# pressure.net
KiCad netlist of a schematic drawn in EAGLE
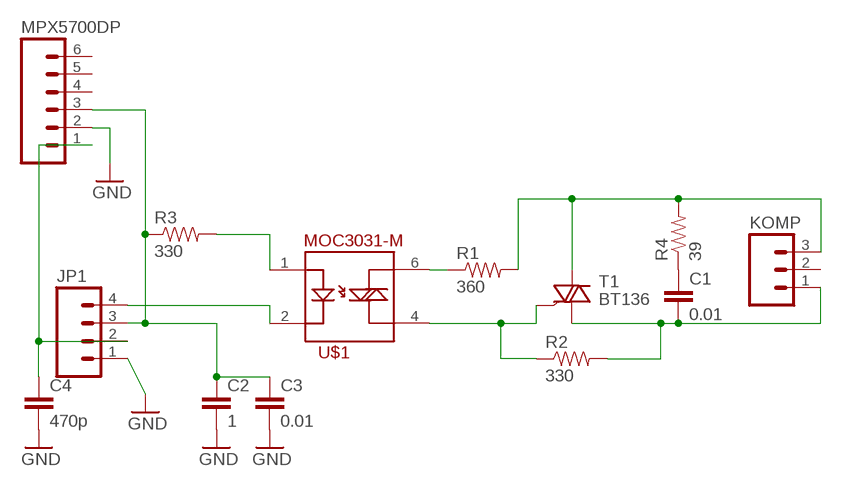
[diagram p0: schematic, sheet 1]

(export (version "E")
  (design (tool "Eeschema 10.0.6"))
  (components
    (comp (ref "C1")
      (value "0.01")
      (footprint "eagle-import:CAP-PTH-5MM")
      (libsource (lib "eagle-import") (part "CAPPTH1"))
    )
    (comp (ref "C2")
      (value "1")
      (footprint "eagle-import:CAP-PTH-5MM")
      (libsource (lib "eagle-import") (part "CAPPTH1"))
    )
    (comp (ref "C3")
      (value "0.01")
      (footprint "eagle-import:CAP-PTH-5MM")
      (libsource (lib "eagle-import") (part "CAPPTH1"))
    )
    (comp (ref "C4")
      (value "470p")
      (footprint "eagle-import:CAP-PTH-5MM")
      (libsource (lib "eagle-import") (part "CAPPTH1"))
    )
    (comp (ref "JP1")
      (value "M04LONGPADS")
      (footprint "eagle-import:1X04_LONGPADS")
      (libsource (lib "eagle-import") (part "M04LONGPADS"))
    )
    (comp (ref "KOMP")
      (value "M03LONGPADS")
      (footprint "eagle-import:1X03_LONGPADS")
      (libsource (lib "eagle-import") (part "M03LONGPADS"))
    )
    (comp (ref "MPX5700DP")
      (value "M06LONGPADS")
      (footprint "eagle-import:1X06_LONGPADS")
      (libsource (lib "eagle-import") (part "M06LONGPADS"))
    )
    (comp (ref "R1")
      (value "360")
      (footprint "eagle-import:AXIAL-0.3-KIT")
      (libsource (lib "eagle-import") (part "RESISTORKIT"))
    )
    (comp (ref "R2")
      (value "330")
      (footprint "eagle-import:AXIAL-0.3-KIT")
      (libsource (lib "eagle-import") (part "RESISTORKIT"))
    )
    (comp (ref "R3")
      (value "330")
      (footprint "eagle-import:AXIAL-0.3-KIT")
      (libsource (lib "eagle-import") (part "RESISTORKIT"))
    )
    (comp (ref "R4")
      (value "39")
      (footprint "eagle-import:AXIAL-0.3-KIT")
      (libsource (lib "eagle-import") (part "RESISTORKIT"))
    )
    (comp (ref "T1")
      (value "BT136")
      (footprint "eagle-import:TO220AB")
      (libsource (lib "eagle-import") (part "BT136"))
    )
    (comp (ref "U$1")
      (value "MOC3031-M")
      (footprint "eagle-import:DIL06")
      (libsource (lib "eagle-import") (part "MOC3031-M"))
    )
  )
  (nets
    (net (code "1") (name "GND") (class "Default")
      (node (ref "C2") (pin "2") (pinfunction "2_2") (pintype "passive"))
      (node (ref "C3") (pin "2") (pinfunction "2_2") (pintype "passive"))
      (node (ref "C4") (pin "2") (pinfunction "2_2") (pintype "passive"))
      (node (ref "JP1") (pin "1") (pinfunction "1_1") (pintype "passive"))
      (node (ref "MPX5700DP") (pin "2") (pinfunction "2_2") (pintype "passive"))
    )
    (net (code "2") (name "Net-(C4-Pad1)") (class "Default")
      (node (ref "C4") (pin "1") (pinfunction "1_1") (pintype "passive"))
      (node (ref "JP1") (pin "2") (pinfunction "2_2") (pintype "passive"))
      (node (ref "MPX5700DP") (pin "1") (pinfunction "1_1") (pintype "passive"))
    )
    (net (code "3") (name "Net-(JP1-Pad4)") (class "Default")
      (node (ref "JP1") (pin "4") (pinfunction "4_4") (pintype "passive"))
      (node (ref "U$1") (pin "2") (pinfunction "2_2") (pintype "bidirectional"))
    )
    (net (code "4") (name "Net-(R1-1)") (class "Default")
      (node (ref "R1") (pin "P$1") (pinfunction "1_P$1") (pintype "passive"))
      (node (ref "U$1") (pin "6") (pinfunction "6_6") (pintype "bidirectional"))
    )
    (net (code "5") (name "Net-(R1-2)") (class "Default")
      (node (ref "KOMP") (pin "3") (pinfunction "3_3") (pintype "passive"))
      (node (ref "R1") (pin "P$2") (pinfunction "2_P$2") (pintype "passive"))
      (node (ref "R4") (pin "P$2") (pinfunction "2_P$2") (pintype "passive"))
      (node (ref "T1") (pin "2") (pinfunction "A2_2") (pintype "passive"))
    )
    (net (code "6") (name "Net-(R2-1)") (class "Default")
      (node (ref "R2") (pin "P$1") (pinfunction "1_P$1") (pintype "passive"))
      (node (ref "T1") (pin "3") (pinfunction "G_3") (pintype "passive"))
      (node (ref "U$1") (pin "4") (pinfunction "4_4") (pintype "bidirectional"))
    )
    (net (code "7") (name "Net-(R2-2)") (class "Default")
      (node (ref "C1") (pin "2") (pinfunction "2_2") (pintype "passive"))
      (node (ref "KOMP") (pin "1") (pinfunction "1_1") (pintype "passive"))
      (node (ref "R2") (pin "P$2") (pinfunction "2_P$2") (pintype "passive"))
      (node (ref "T1") (pin "1") (pinfunction "A1_1") (pintype "passive"))
    )
    (net (code "8") (name "Net-(R3-1)") (class "Default")
      (node (ref "C2") (pin "1") (pinfunction "1_1") (pintype "passive"))
      (node (ref "C3") (pin "1") (pinfunction "1_1") (pintype "passive"))
      (node (ref "JP1") (pin "3") (pinfunction "3_3") (pintype "passive"))
      (node (ref "MPX5700DP") (pin "3") (pinfunction "3_3") (pintype "passive"))
      (node (ref "R3") (pin "P$1") (pinfunction "1_P$1") (pintype "passive"))
    )
    (net (code "9") (name "Net-(R3-2)") (class "Default")
      (node (ref "R3") (pin "P$2") (pinfunction "2_P$2") (pintype "passive"))
      (node (ref "U$1") (pin "1") (pinfunction "1_1") (pintype "bidirectional"))
    )
    (net (code "10") (name "Net-(R4-1)") (class "Default")
      (node (ref "C1") (pin "1") (pinfunction "1_1") (pintype "passive"))
      (node (ref "R4") (pin "P$1") (pinfunction "1_P$1") (pintype "passive"))
    )
    (net (code "11") (name "unconnected-(KOMP-Pad2)") (class "Default")
      (node (ref "KOMP") (pin "2") (pinfunction "2_2") (pintype "passive"))
    )
    (net (code "12") (name "unconnected-(MPX5700DP-Pad4)") (class "Default")
      (node (ref "MPX5700DP") (pin "4") (pinfunction "4_4") (pintype "passive"))
    )
    (net (code "13") (name "unconnected-(MPX5700DP-Pad5)") (class "Default")
      (node (ref "MPX5700DP") (pin "5") (pinfunction "5_5") (pintype "passive"))
    )
    (net (code "14") (name "unconnected-(MPX5700DP-Pad6)") (class "Default")
      (node (ref "MPX5700DP") (pin "6") (pinfunction "6_6") (pintype "passive"))
    )
  )
)
